# Lucette_V05.net
KiCad netlist of a schematic drawn in EAGLE
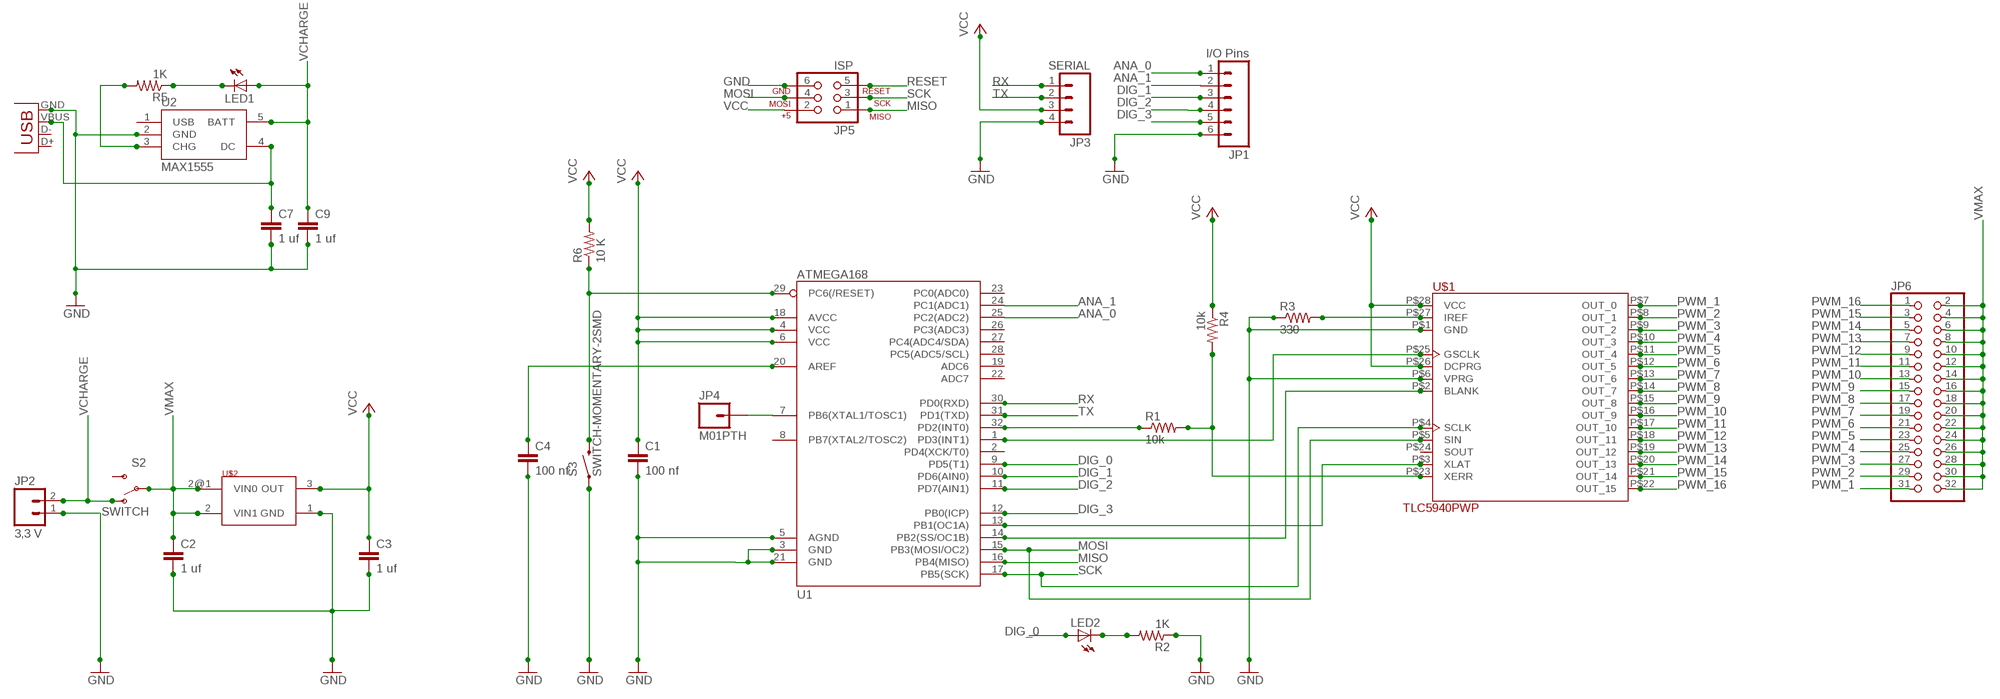
[diagram p0: schematic, sheet 1]

(export (version "E")
  (design (tool "Eeschema 10.0.6"))
  (components
    (comp (ref "C1")
      (value "100 nf")
      (footprint "eagle-import:0805")
      (libsource (lib "eagle-import") (part "CAP0805"))
    )
    (comp (ref "C2")
      (value "1 uf")
      (footprint "eagle-import:0805")
      (libsource (lib "eagle-import") (part "CAP0805"))
    )
    (comp (ref "C3")
      (value "1 uf")
      (footprint "eagle-import:0805")
      (libsource (lib "eagle-import") (part "CAP0805"))
    )
    (comp (ref "C4")
      (value "100 nf")
      (footprint "eagle-import:0805")
      (libsource (lib "eagle-import") (part "CAP0805"))
    )
    (comp (ref "C7")
      (value "1 uf")
      (footprint "eagle-import:0805")
      (libsource (lib "eagle-import") (part "CAP0805"))
    )
    (comp (ref "C9")
      (value "1 uf")
      (footprint "eagle-import:0805")
      (libsource (lib "eagle-import") (part "CAP0805"))
    )
    (comp (ref "JP1")
      (value "I/O Pins")
      (footprint "eagle-import:1X06-SMD")
      (libsource (lib "eagle-import") (part "M06SMD"))
    )
    (comp (ref "JP2")
      (value "3,3 V")
      (footprint "eagle-import:S2B-PH")
      (libsource (lib "eagle-import") (part "M02-JST-2MM-SMT"))
    )
    (comp (ref "JP3")
      (value "SERIAL")
      (footprint "eagle-import:1X04-SMD")
      (libsource (lib "eagle-import") (part "M04SMD"))
    )
    (comp (ref "JP4")
      (value "M01PTH")
      (footprint "eagle-import:1X01")
      (libsource (lib "eagle-import") (part "M01PTH"))
    )
    (comp (ref "JP5")
      (value "ISP")
      (footprint "eagle-import:2X3")
      (libsource (lib "eagle-import") (part "AVR_SPI_PRG_6PTH"))
    )
    (comp (ref "JP6")
      (value "PINHD-2X16/90")
      (footprint "eagle-import:2X16_90")
      (libsource (lib "eagle-import") (part "PINHD-2X16/90"))
    )
    (comp (ref "LED1")
      (value "LEDCHIP-LED0805")
      (footprint "eagle-import:CHIP-LED0805")
      (libsource (lib "eagle-import") (part "LEDCHIP-LED0805"))
    )
    (comp (ref "LED2")
      (value "LEDCHIP-LED0805")
      (footprint "eagle-import:CHIP-LED0805")
      (libsource (lib "eagle-import") (part "LEDCHIP-LED0805"))
    )
    (comp (ref "R1")
      (value "10k")
      (footprint "eagle-import:1206")
      (libsource (lib "eagle-import") (part "RESISTOR1206"))
    )
    (comp (ref "R2")
      (value "1K")
      (footprint "eagle-import:1206")
      (libsource (lib "eagle-import") (part "RESISTOR1206"))
    )
    (comp (ref "R3")
      (value "330")
      (footprint "eagle-import:1206")
      (libsource (lib "eagle-import") (part "RESISTOR1206"))
    )
    (comp (ref "R4")
      (value "10k")
      (footprint "eagle-import:1206")
      (libsource (lib "eagle-import") (part "RESISTOR1206"))
    )
    (comp (ref "R5")
      (value "1K")
      (footprint "eagle-import:1206")
      (libsource (lib "eagle-import") (part "RESISTOR1206"))
    )
    (comp (ref "R6")
      (value "10 K")
      (footprint "eagle-import:1206")
      (libsource (lib "eagle-import") (part "RESISTOR1206"))
    )
    (comp (ref "S2")
      (value "SWITCH")
      (footprint "eagle-import:AYZ0202")
      (libsource (lib "eagle-import") (part "SWITCH-SPSTSMD"))
    )
    (comp (ref "S3")
      (value "SWITCH-MOMENTARY-2SMD")
      (footprint "eagle-import:TACTILE_SWITCH_SMD")
      (libsource (lib "eagle-import") (part "SWITCH-MOMENTARY-2SMD"))
    )
    (comp (ref "U$1")
      (value "TLC5940PWP")
      (footprint "eagle-import:PWP-28")
      (libsource (lib "eagle-import") (part "TLC5940PWP"))
    )
    (comp (ref "U$2")
      (value "MCP1703")
      (footprint "eagle-import:SOT98")
      (libsource (lib "eagle-import") (part "MCP1703"))
    )
    (comp (ref "U1")
      (value "ATMEGA168")
      (footprint "eagle-import:TQFP32-08")
      (libsource (lib "eagle-import") (part "ATMEGA168"))
    )
    (comp (ref "U2")
      (value "MAX1555")
      (footprint "eagle-import:SOT23-5")
      (libsource (lib "eagle-import") (part "MAX1555"))
    )
    (comp (ref "X1")
      (value "USBOLD")
      (footprint "eagle-import:USB-MINIB-OLD")
      (libsource (lib "eagle-import") (part "USBOLD"))
    )
  )
  (nets
    (net (code "1") (name "/ANA_0") (class "Default")
      (node (ref "JP1") (pin "1") (pinfunction "1_1") (pintype "passive"))
      (node (ref "U1") (pin "25") (pinfunction "PC2(ADC2)_25") (pintype "bidirectional"))
    )
    (net (code "2") (name "/ANA_1") (class "Default")
      (node (ref "JP1") (pin "2") (pinfunction "2_2") (pintype "passive"))
      (node (ref "U1") (pin "24") (pinfunction "PC1(ADC1)_24") (pintype "bidirectional"))
    )
    (net (code "3") (name "/DIG_0") (class "Default")
      (node (ref "LED2") (pin "A") (pinfunction "A_A") (pintype "passive"))
      (node (ref "U1") (pin "9") (pinfunction "PD5(T1)_9") (pintype "bidirectional"))
    )
    (net (code "4") (name "/DIG_1") (class "Default")
      (node (ref "JP1") (pin "3") (pinfunction "3_3") (pintype "passive"))
      (node (ref "U1") (pin "10") (pinfunction "PD6(AIN0)_10") (pintype "bidirectional"))
    )
    (net (code "5") (name "/DIG_2") (class "Default")
      (node (ref "JP1") (pin "4") (pinfunction "4_4") (pintype "passive"))
      (node (ref "U1") (pin "11") (pinfunction "PD7(AIN1)_11") (pintype "bidirectional"))
    )
    (net (code "6") (name "/DIG_3") (class "Default")
      (node (ref "JP1") (pin "5") (pinfunction "5_5") (pintype "passive"))
      (node (ref "U1") (pin "12") (pinfunction "PB0(ICP)_12") (pintype "bidirectional"))
    )
    (net (code "7") (name "/MISO") (class "Default")
      (node (ref "JP5") (pin "1") (pinfunction "1_1") (pintype "passive"))
      (node (ref "U1") (pin "16") (pinfunction "PB4(MISO)_16") (pintype "bidirectional"))
    )
    (net (code "8") (name "/MOSI") (class "Default")
      (node (ref "JP5") (pin "4") (pinfunction "4_4") (pintype "passive"))
      (node (ref "U$1") (pin "P$5") (pinfunction "SIN_P$5") (pintype "input"))
      (node (ref "U1") (pin "15") (pinfunction "PB3(MOSI/OC2)_15") (pintype "bidirectional"))
    )
    (net (code "9") (name "/PWM_1") (class "Default")
      (node (ref "JP6") (pin "31") (pinfunction "31_31") (pintype "passive"))
      (node (ref "U$1") (pin "P$7") (pinfunction "OUT_0_P$7") (pintype "output"))
    )
    (net (code "10") (name "/PWM_2") (class "Default")
      (node (ref "JP6") (pin "29") (pinfunction "29_29") (pintype "passive"))
      (node (ref "U$1") (pin "P$8") (pinfunction "OUT_1_P$8") (pintype "output"))
    )
    (net (code "11") (name "/PWM_3") (class "Default")
      (node (ref "JP6") (pin "27") (pinfunction "27_27") (pintype "passive"))
      (node (ref "U$1") (pin "P$9") (pinfunction "OUT_2_P$9") (pintype "output"))
    )
    (net (code "12") (name "/PWM_4") (class "Default")
      (node (ref "JP6") (pin "25") (pinfunction "25_25") (pintype "passive"))
      (node (ref "U$1") (pin "P$10") (pinfunction "OUT_3_P$10") (pintype "output"))
    )
    (net (code "13") (name "/PWM_5") (class "Default")
      (node (ref "JP6") (pin "23") (pinfunction "23_23") (pintype "passive"))
      (node (ref "U$1") (pin "P$11") (pinfunction "OUT_4_P$11") (pintype "output"))
    )
    (net (code "14") (name "/PWM_6") (class "Default")
      (node (ref "JP6") (pin "21") (pinfunction "21_21") (pintype "passive"))
      (node (ref "U$1") (pin "P$12") (pinfunction "OUT_5_P$12") (pintype "output"))
    )
    (net (code "15") (name "/PWM_7") (class "Default")
      (node (ref "JP6") (pin "19") (pinfunction "19_19") (pintype "passive"))
      (node (ref "U$1") (pin "P$13") (pinfunction "OUT_6_P$13") (pintype "output"))
    )
    (net (code "16") (name "/PWM_8") (class "Default")
      (node (ref "JP6") (pin "17") (pinfunction "17_17") (pintype "passive"))
      (node (ref "U$1") (pin "P$14") (pinfunction "OUT_7_P$14") (pintype "output"))
    )
    (net (code "17") (name "/PWM_9") (class "Default")
      (node (ref "JP6") (pin "15") (pinfunction "15_15") (pintype "passive"))
      (node (ref "U$1") (pin "P$15") (pinfunction "OUT_8_P$15") (pintype "output"))
    )
    (net (code "18") (name "/PWM_10") (class "Default")
      (node (ref "JP6") (pin "13") (pinfunction "13_13") (pintype "passive"))
      (node (ref "U$1") (pin "P$16") (pinfunction "OUT_9_P$16") (pintype "output"))
    )
    (net (code "19") (name "/PWM_11") (class "Default")
      (node (ref "JP6") (pin "11") (pinfunction "11_11") (pintype "passive"))
      (node (ref "U$1") (pin "P$17") (pinfunction "OUT_10_P$17") (pintype "output"))
    )
    (net (code "20") (name "/PWM_12") (class "Default")
      (node (ref "JP6") (pin "9") (pinfunction "9_9") (pintype "passive"))
      (node (ref "U$1") (pin "P$18") (pinfunction "OUT_11_P$18") (pintype "output"))
    )
    (net (code "21") (name "/PWM_13") (class "Default")
      (node (ref "JP6") (pin "7") (pinfunction "7_7") (pintype "passive"))
      (node (ref "U$1") (pin "P$19") (pinfunction "OUT_12_P$19") (pintype "output"))
    )
    (net (code "22") (name "/PWM_14") (class "Default")
      (node (ref "JP6") (pin "5") (pinfunction "5_5") (pintype "passive"))
      (node (ref "U$1") (pin "P$20") (pinfunction "OUT_13_P$20") (pintype "output"))
    )
    (net (code "23") (name "/PWM_15") (class "Default")
      (node (ref "JP6") (pin "3") (pinfunction "3_3") (pintype "passive"))
      (node (ref "U$1") (pin "P$21") (pinfunction "OUT_14_P$21") (pintype "output"))
    )
    (net (code "24") (name "/PWM_16") (class "Default")
      (node (ref "JP6") (pin "1") (pinfunction "1_1") (pintype "passive"))
      (node (ref "U$1") (pin "P$22") (pinfunction "OUT_15_P$22") (pintype "output"))
    )
    (net (code "25") (name "/RESET") (class "Default")
      (node (ref "JP5") (pin "5") (pinfunction "5_5") (pintype "passive"))
      (node (ref "R6") (pin "1") (pinfunction "1_1") (pintype "passive"))
      (node (ref "S3") (pin "3") (pinfunction "2_3") (pintype "passive"))
      (node (ref "U1") (pin "29") (pinfunction "PC6(/RESET)_29") (pintype "bidirectional"))
    )
    (net (code "26") (name "/RX") (class "Default")
      (node (ref "JP3") (pin "1") (pinfunction "1_1") (pintype "passive"))
      (node (ref "U1") (pin "30") (pinfunction "PD0(RXD)_30") (pintype "bidirectional"))
    )
    (net (code "27") (name "/SCK") (class "Default")
      (node (ref "JP5") (pin "3") (pinfunction "3_3") (pintype "passive"))
      (node (ref "U$1") (pin "P$4") (pinfunction "SCLK_P$4") (pintype "input"))
      (node (ref "U1") (pin "17") (pinfunction "PB5(SCK)_17") (pintype "bidirectional"))
    )
    (net (code "28") (name "/TX") (class "Default")
      (node (ref "JP3") (pin "2") (pinfunction "2_2") (pintype "passive"))
      (node (ref "U1") (pin "31") (pinfunction "PD1(TXD)_31") (pintype "bidirectional"))
    )
    (net (code "29") (name "/VCHARGE") (class "Default")
      (node (ref "C9") (pin "1") (pinfunction "1_1") (pintype "passive"))
      (node (ref "JP2") (pin "2") (pinfunction "2_2") (pintype "passive"))
      (node (ref "LED1") (pin "A") (pinfunction "A_A") (pintype "passive"))
      (node (ref "S2") (pin "1") (pinfunction "O_1") (pintype "passive"))
      (node (ref "U2") (pin "5") (pinfunction "BATT_5") (pintype "bidirectional"))
    )
    (net (code "30") (name "/VMAX") (class "Default")
      (node (ref "C2") (pin "1") (pinfunction "1_1") (pintype "passive"))
      (node (ref "JP6") (pin "10") (pinfunction "10_10") (pintype "passive"))
      (node (ref "JP6") (pin "12") (pinfunction "12_12") (pintype "passive"))
      (node (ref "JP6") (pin "14") (pinfunction "14_14") (pintype "passive"))
      (node (ref "JP6") (pin "16") (pinfunction "16_16") (pintype "passive"))
      (node (ref "JP6") (pin "18") (pinfunction "18_18") (pintype "passive"))
      (node (ref "JP6") (pin "2") (pinfunction "2_2") (pintype "passive"))
      (node (ref "JP6") (pin "20") (pinfunction "20_20") (pintype "passive"))
      (node (ref "JP6") (pin "22") (pinfunction "22_22") (pintype "passive"))
      (node (ref "JP6") (pin "24") (pinfunction "24_24") (pintype "passive"))
      (node (ref "JP6") (pin "26") (pinfunction "26_26") (pintype "passive"))
      (node (ref "JP6") (pin "28") (pinfunction "28_28") (pintype "passive"))
      (node (ref "JP6") (pin "30") (pinfunction "30_30") (pintype "passive"))
      (node (ref "JP6") (pin "32") (pinfunction "32_32") (pintype "passive"))
      (node (ref "JP6") (pin "4") (pinfunction "4_4") (pintype "passive"))
      (node (ref "JP6") (pin "6") (pinfunction "6_6") (pintype "passive"))
      (node (ref "JP6") (pin "8") (pinfunction "8_8") (pintype "passive"))
      (node (ref "S2") (pin "2") (pinfunction "P_2") (pintype "passive"))
      (node (ref "U$2") (pin "2") (pinfunction "VIN1_2") (pintype "bidirectional"))
      (node (ref "U$2") (pin "2@1") (pinfunction "VIN0_2@1") (pintype "bidirectional"))
    )
    (net (code "31") (name "GND") (class "Default")
      (node (ref "C1") (pin "2") (pinfunction "2_2") (pintype "passive"))
      (node (ref "C2") (pin "2") (pinfunction "2_2") (pintype "passive"))
      (node (ref "C3") (pin "2") (pinfunction "2_2") (pintype "passive"))
      (node (ref "C4") (pin "2") (pinfunction "2_2") (pintype "passive"))
      (node (ref "C7") (pin "2") (pinfunction "2_2") (pintype "passive"))
      (node (ref "C9") (pin "2") (pinfunction "2_2") (pintype "passive"))
      (node (ref "JP1") (pin "6") (pinfunction "6_6") (pintype "passive"))
      (node (ref "JP2") (pin "1") (pinfunction "1_1") (pintype "passive"))
      (node (ref "JP3") (pin "4") (pinfunction "4_4") (pintype "passive"))
      (node (ref "JP5") (pin "6") (pinfunction "6_6") (pintype "passive"))
      (node (ref "R2") (pin "1") (pinfunction "1_1") (pintype "passive"))
      (node (ref "R3") (pin "1") (pinfunction "1_1") (pintype "passive"))
      (node (ref "S3") (pin "1") (pinfunction "1_1") (pintype "passive"))
      (node (ref "U$1") (pin "P$1") (pinfunction "GND_P$1") (pintype "power_in"))
      (node (ref "U$1") (pin "P$6") (pinfunction "VPRG_P$6") (pintype "input"))
      (node (ref "U$2") (pin "1") (pinfunction "GND_1") (pintype "bidirectional"))
      (node (ref "U1") (pin "21") (pinfunction "GND_21") (pintype "bidirectional"))
      (node (ref "U1") (pin "3") (pinfunction "GND_3") (pintype "bidirectional"))
      (node (ref "U1") (pin "5") (pinfunction "AGND_5") (pintype "bidirectional"))
      (node (ref "U2") (pin "2") (pinfunction "GND_2") (pintype "bidirectional"))
      (node (ref "X1") (pin "GND") (pinfunction "GND_GND") (pintype "bidirectional"))
    )
    (net (code "32") (name "Net-(LED1-PadC)") (class "Default")
      (node (ref "LED1") (pin "C") (pinfunction "C_C") (pintype "passive"))
      (node (ref "R5") (pin "1") (pinfunction "1_1") (pintype "passive"))
    )
    (net (code "33") (name "Net-(LED2-PadC)") (class "Default")
      (node (ref "LED2") (pin "C") (pinfunction "C_C") (pintype "passive"))
      (node (ref "R2") (pin "2") (pinfunction "2_2") (pintype "passive"))
    )
    (net (code "34") (name "Net-(U$1-BLANK)") (class "Default")
      (node (ref "U$1") (pin "P$2") (pinfunction "BLANK_P$2") (pintype "input"))
      (node (ref "U1") (pin "14") (pinfunction "PB2(SS/OC1B)_14") (pintype "bidirectional"))
    )
    (net (code "35") (name "Net-(U$1-GSCLK)") (class "Default")
      (node (ref "U$1") (pin "P$25") (pinfunction "GSCLK_P$25") (pintype "input"))
      (node (ref "U1") (pin "1") (pinfunction "PD3(INT1)_1") (pintype "bidirectional"))
    )
    (net (code "36") (name "Net-(U$1-IREF)") (class "Default")
      (node (ref "R3") (pin "2") (pinfunction "2_2") (pintype "passive"))
      (node (ref "U$1") (pin "P$27") (pinfunction "IREF_P$27") (pintype "power_in"))
    )
    (net (code "37") (name "Net-(U$1-XERR)") (class "Default")
      (node (ref "R1") (pin "2") (pinfunction "2_2") (pintype "passive"))
      (node (ref "R4") (pin "2") (pinfunction "2_2") (pintype "passive"))
      (node (ref "U$1") (pin "P$23") (pinfunction "XERR_P$23") (pintype "output"))
    )
    (net (code "38") (name "Net-(U$1-XLAT)") (class "Default")
      (node (ref "U$1") (pin "P$3") (pinfunction "XLAT_P$3") (pintype "input"))
      (node (ref "U1") (pin "13") (pinfunction "PB1(OC1A)_13") (pintype "bidirectional"))
    )
    (net (code "39") (name "Net-(U1-AREF)") (class "Default")
      (node (ref "C4") (pin "1") (pinfunction "1_1") (pintype "passive"))
      (node (ref "U1") (pin "20") (pinfunction "AREF_20") (pintype "bidirectional"))
    )
    (net (code "40") (name "Net-(U1-PB6(XTAL1{slash}TOSC1))") (class "Default")
      (node (ref "JP4") (pin "1") (pinfunction "1_1") (pintype "passive"))
      (node (ref "U1") (pin "7") (pinfunction "PB6(XTAL1/TOSC1)_7") (pintype "bidirectional"))
    )
    (net (code "41") (name "Net-(U1-PD2(INT0))") (class "Default")
      (node (ref "R1") (pin "1") (pinfunction "1_1") (pintype "passive"))
      (node (ref "U1") (pin "32") (pinfunction "PD2(INT0)_32") (pintype "bidirectional"))
    )
    (net (code "42") (name "Net-(U2-CHG)") (class "Default")
      (node (ref "R5") (pin "2") (pinfunction "2_2") (pintype "passive"))
      (node (ref "U2") (pin "3") (pinfunction "CHG_3") (pintype "bidirectional"))
    )
    (net (code "43") (name "Net-(U2-DC)") (class "Default")
      (node (ref "C7") (pin "1") (pinfunction "1_1") (pintype "passive"))
      (node (ref "U2") (pin "4") (pinfunction "DC_4") (pintype "bidirectional"))
      (node (ref "X1") (pin "VBUS") (pinfunction "VBUS_VBUS") (pintype "bidirectional"))
    )
    (net (code "44") (name "VCC") (class "Default")
      (node (ref "C1") (pin "1") (pinfunction "1_1") (pintype "passive"))
      (node (ref "C3") (pin "1") (pinfunction "1_1") (pintype "passive"))
      (node (ref "JP3") (pin "3") (pinfunction "3_3") (pintype "passive"))
      (node (ref "JP5") (pin "2") (pinfunction "2_2") (pintype "passive"))
      (node (ref "R4") (pin "1") (pinfunction "1_1") (pintype "passive"))
      (node (ref "R6") (pin "2") (pinfunction "2_2") (pintype "passive"))
      (node (ref "U$1") (pin "P$26") (pinfunction "DCPRG_P$26") (pintype "input"))
      (node (ref "U$1") (pin "P$28") (pinfunction "VCC_P$28") (pintype "power_in"))
      (node (ref "U$2") (pin "3") (pinfunction "OUT_3") (pintype "bidirectional"))
      (node (ref "U1") (pin "18") (pinfunction "AVCC_18") (pintype "bidirectional"))
      (node (ref "U1") (pin "4") (pinfunction "VCC_4") (pintype "bidirectional"))
      (node (ref "U1") (pin "6") (pinfunction "VCC_6") (pintype "bidirectional"))
    )
    (net (code "45") (name "unconnected-(S2-S-Pad3)") (class "Default")
      (node (ref "S2") (pin "3") (pinfunction "S_3") (pintype "passive"))
    )
    (net (code "46") (name "unconnected-(U$1-SOUT-PadP$24)") (class "Default")
      (node (ref "U$1") (pin "P$24") (pinfunction "SOUT_P$24") (pintype "output"))
    )
    (net (code "47") (name "unconnected-(U1-ADC6-Pad19)") (class "Default")
      (node (ref "U1") (pin "19") (pinfunction "ADC6_19") (pintype "bidirectional"))
    )
    (net (code "48") (name "unconnected-(U1-ADC7-Pad22)") (class "Default")
      (node (ref "U1") (pin "22") (pinfunction "ADC7_22") (pintype "bidirectional"))
    )
    (net (code "49") (name "unconnected-(U1-PB7(XTAL2{slash}TOSC2)-Pad8)") (class "Default")
      (node (ref "U1") (pin "8") (pinfunction "PB7(XTAL2/TOSC2)_8") (pintype "bidirectional"))
    )
    (net (code "50") (name "unconnected-(U1-PC0(ADC0)-Pad23)") (class "Default")
      (node (ref "U1") (pin "23") (pinfunction "PC0(ADC0)_23") (pintype "bidirectional"))
    )
    (net (code "51") (name "unconnected-(U1-PC3(ADC3)-Pad26)") (class "Default")
      (node (ref "U1") (pin "26") (pinfunction "PC3(ADC3)_26") (pintype "bidirectional"))
    )
    (net (code "52") (name "unconnected-(U1-PC4(ADC4{slash}SDA)-Pad27)") (class "Default")
      (node (ref "U1") (pin "27") (pinfunction "PC4(ADC4/SDA)_27") (pintype "bidirectional"))
    )
    (net (code "53") (name "unconnected-(U1-PC5(ADC5{slash}SCL)-Pad28)") (class "Default")
      (node (ref "U1") (pin "28") (pinfunction "PC5(ADC5/SCL)_28") (pintype "bidirectional"))
    )
    (net (code "54") (name "unconnected-(U1-PD4(XCK{slash}T0)-Pad2)") (class "Default")
      (node (ref "U1") (pin "2") (pinfunction "PD4(XCK/T0)_2") (pintype "bidirectional"))
    )
    (net (code "55") (name "unconnected-(U2-USB-Pad1)") (class "Default")
      (node (ref "U2") (pin "1") (pinfunction "USB_1") (pintype "bidirectional"))
    )
    (net (code "56") (name "unconnected-(X1-PadD+)") (class "Default")
      (node (ref "X1") (pin "D+") (pinfunction "D+_D+") (pintype "bidirectional"))
    )
    (net (code "57") (name "unconnected-(X1-PadD-)") (class "Default")
      (node (ref "X1") (pin "D-") (pinfunction "D-_D-") (pintype "bidirectional"))
    )
  )
)
